# power_supply.net
KiCad netlist of a schematic drawn in Altium Designer
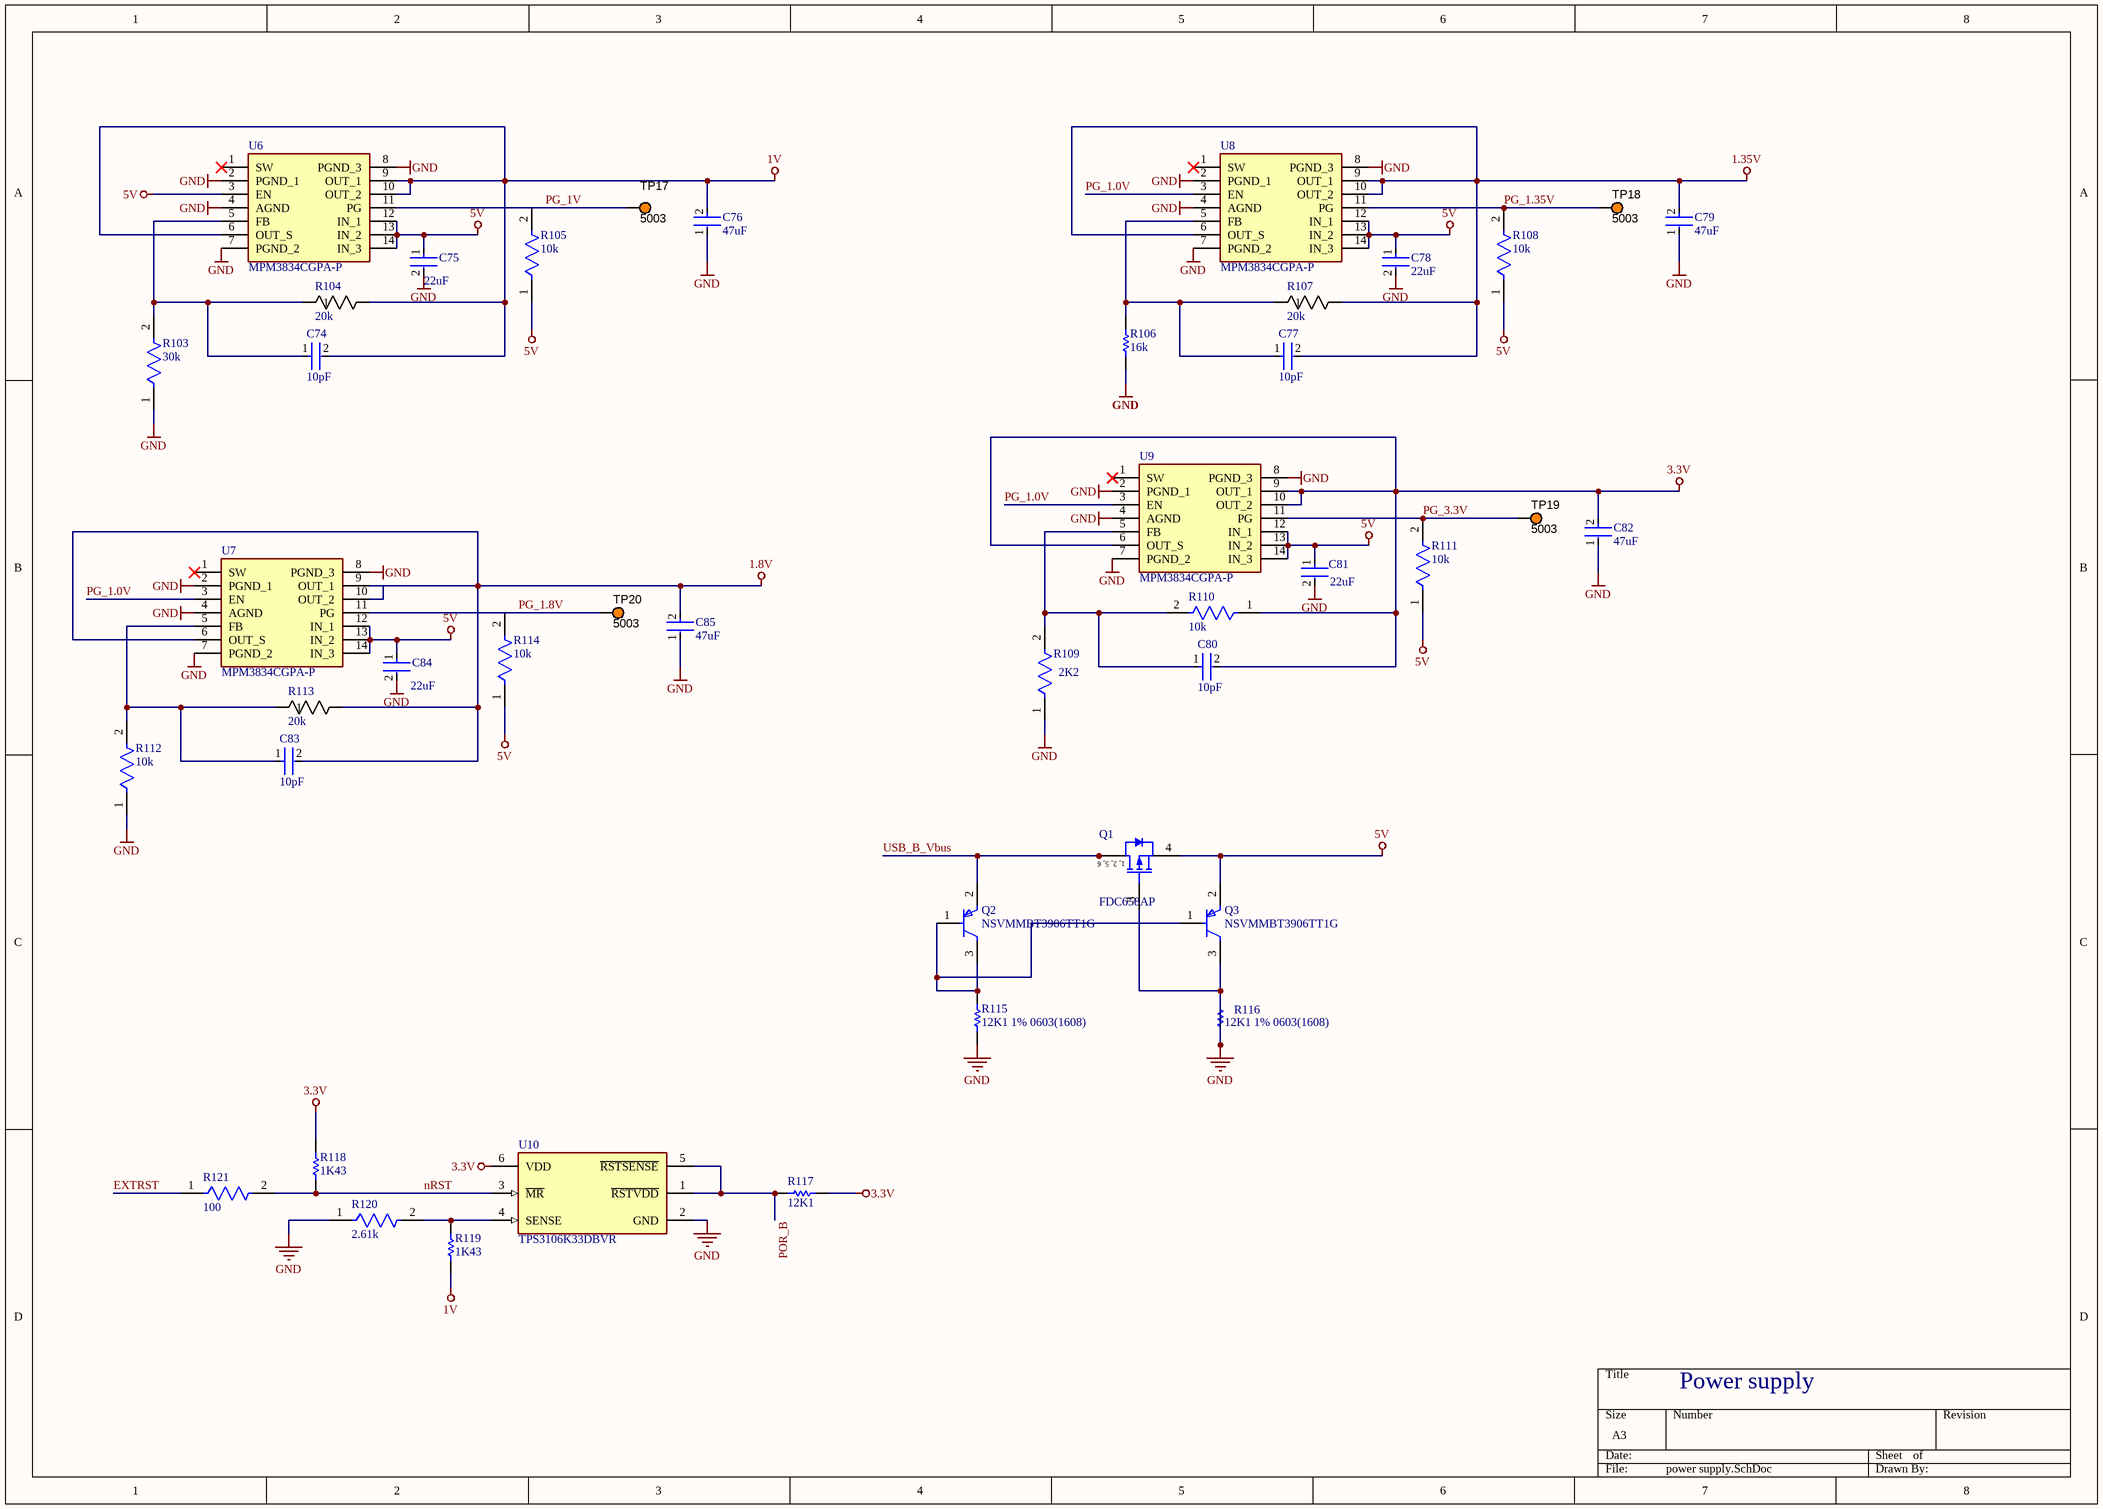
[diagram p0: power supply.SchDoc]

(export (version "E")
  (design (tool "Eeschema 10.0.6"))
  (components
    (comp (ref "C74")
      (value "10pF")
      (footprint "FP-0603-L_1_6_0_15-W_0_81-IPC_B")
      (description "General Purpose Ceramic Capacitor, 0603, 10pF, 2%, NP0, 30ppm/°C, 100V")
      (fields (field (name "TOLERANCE") "2%"))
      (libsource (lib "Altium Content Vault") (part "02cd4be3c70576c341d710602a673aa"))
    )
    (comp (ref "C75")
      (value "22uF")
      (footprint "FP-GRMJN7-0_1-IPC_C")
      (description "Chip Multilayer Ceramic Capacitors for General Purpose, 0704, 22uF, X5R, 15%, 20%, 16V")
      (libsource (lib "Altium Content Vault") (part "02cd4be3c70576c341d710602a673aa"))
    )
    (comp (ref "C76")
      (value "47uF")
      (footprint "FP-GRM31C-0_3-e0_3_0_8-IPC_C")
      (description "Chip Multilayer Ceramic Capacitors for General Purpose, 1206, 47uF, X5R, 15%, 20%, 16V")
      (fields (field (name "TOLERANCE") "20%"))
      (libsource (lib "Altium Content Vault") (part "f23184f103b6ebe33a8c269c53dcba6"))
    )
    (comp (ref "C77")
      (value "10pF")
      (footprint "FP-0603-L_1_6_0_15-W_0_81-IPC_B")
      (description "General Purpose Ceramic Capacitor, 0603, 10pF, 2%, NP0, 30ppm/°C, 100V")
      (fields (field (name "TOLERANCE") "2%"))
      (libsource (lib "Altium Content Vault") (part "02cd4be3c70576c341d710602a673aa"))
    )
    (comp (ref "C78")
      (value "22uF")
      (footprint "FP-GRMJN7-0_1-IPC_C")
      (description "Chip Multilayer Ceramic Capacitors for General Purpose, 0704, 22uF, X5R, 15%, 20%, 16V")
      (libsource (lib "Altium Content Vault") (part "02cd4be3c70576c341d710602a673aa"))
    )
    (comp (ref "C79")
      (value "47uF")
      (footprint "FP-GRM31C-0_3-e0_3_0_8-IPC_C")
      (description "Chip Multilayer Ceramic Capacitors for General Purpose, 1206, 47uF, X5R, 15%, 20%, 16V")
      (fields (field (name "TOLERANCE") "20%"))
      (libsource (lib "Altium Content Vault") (part "f23184f103b6ebe33a8c269c53dcba6"))
    )
    (comp (ref "C80")
      (value "10pF")
      (footprint "FP-0603-L_1_6_0_15-W_0_81-IPC_B")
      (description "General Purpose Ceramic Capacitor, 0603, 10pF, 2%, NP0, 30ppm/°C, 100V")
      (fields (field (name "TOLERANCE") "2%"))
      (libsource (lib "Altium Content Vault") (part "02cd4be3c70576c341d710602a673aa"))
    )
    (comp (ref "C81")
      (value "22uF")
      (footprint "FP-GRMJN7-0_1-IPC_C")
      (description "Chip Multilayer Ceramic Capacitors for General Purpose, 0704, 22uF, X5R, 15%, 20%, 16V")
      (libsource (lib "Altium Content Vault") (part "02cd4be3c70576c341d710602a673aa"))
    )
    (comp (ref "C82")
      (value "47uF")
      (footprint "FP-GRM31C-0_3-e0_3_0_8-IPC_C")
      (description "Chip Multilayer Ceramic Capacitors for General Purpose, 1206, 47uF, X5R, 15%, 20%, 16V")
      (fields (field (name "TOLERANCE") "20%"))
      (libsource (lib "Altium Content Vault") (part "f23184f103b6ebe33a8c269c53dcba6"))
    )
    (comp (ref "C83")
      (value "10pF")
      (footprint "FP-0603-L_1_6_0_15-W_0_81-IPC_B")
      (description "General Purpose Ceramic Capacitor, 0603, 10pF, 2%, NP0, 30ppm/°C, 100V")
      (fields (field (name "TOLERANCE") "2%"))
      (libsource (lib "Altium Content Vault") (part "02cd4be3c70576c341d710602a673aa"))
    )
    (comp (ref "C84")
      (value "22uF")
      (footprint "FP-GRMJN7-0_1-IPC_C")
      (description "Chip Multilayer Ceramic Capacitors for General Purpose, 0704, 22uF, X5R, 15%, 20%, 16V")
      (libsource (lib "Altium Content Vault") (part "02cd4be3c70576c341d710602a673aa"))
    )
    (comp (ref "C85")
      (value "47uF")
      (footprint "FP-GRM31C-0_3-e0_3_0_8-IPC_C")
      (description "Chip Multilayer Ceramic Capacitors for General Purpose, 1206, 47uF, X5R, 15%, 20%, 16V")
      (fields (field (name "TOLERANCE") "20%"))
      (libsource (lib "Altium Content Vault") (part "f23184f103b6ebe33a8c269c53dcba6"))
    )
    (comp (ref "Q1")
      (value "FDC658AP")
      (footprint "FAIR-SOT23-6_V")
      (fields (field (name "MANUFACTURER") "Fairchild Semiconductor"))
      (libsource (lib "Altium Content Vault") (part "PEMOS-DDGSDD-6"))
    )
    (comp (ref "Q2")
      (value "NSVMMBT3906TT1G")
      (footprint "FP-463-01-MFG")
      (description "NSVMMBT3906TT1G Small Signal Bipolar Transistor, 0.2A I(C), 40V V(BR)CEO, 1-Element, PNP, Silicon")
      (libsource (lib "Altium Content Vault") (part "ffd30bc5d0a750d7d7ef0ebafdf4ab0"))
    )
    (comp (ref "Q3")
      (value "NSVMMBT3906TT1G")
      (footprint "FP-463-01-MFG")
      (description "NSVMMBT3906TT1G Small Signal Bipolar Transistor, 0.2A I(C), 40V V(BR)CEO, 1-Element, PNP, Silicon")
      (libsource (lib "Altium Content Vault") (part "ffd30bc5d0a750d7d7ef0ebafdf4ab0"))
    )
    (comp (ref "R103")
      (value "30k")
      (footprint "FP-RMCF0603-IPC_A")
      (description "30kΩ ±5% 0.1W 0603 Thick Film Chip Resistor AEC-Q200 compliant")
      (fields (field (name "TOLERANCE") "5%"))
      (libsource (lib "Altium Content Vault") (part "1029c3af85768c4190bb7ad29bc67b5"))
    )
    (comp (ref "R104")
      (value "20k")
      (footprint "RES_RCC0402_VIS")
      (description "RCC040220K0FKED Res Thick Film 0402 20K Ohm 1% 0.125W(1/8W) ±100ppm/°C Pad SMD Automotive T/R")
      (libsource (lib "Altium Content Vault") (part "RCC040220K0FKED"))
    )
    (comp (ref "R105")
      (value "10k")
      (footprint "FP-RN73R2A-IPC_A")
      (description "RES 10K OHM 0.1% 1/8W 0805")
      (libsource (lib "Altium Content Vault") (part "1029c3af85768c4190bb7ad29bc67b5"))
    )
    (comp (ref "R106")
      (value "16k")
      (footprint "RESC0603X28X15LL05T05")
      (fields (field (name "PART NUMBER") "CRCW020116K0JNED") (field (name "MANUFACTURER") "Vishay Dale"))
      (libsource (lib "Altium Content Vault") (part "RES"))
    )
    (comp (ref "R107")
      (value "20k")
      (footprint "RES_RCC0402_VIS")
      (description "RCC040220K0FKED Res Thick Film 0402 20K Ohm 1% 0.125W(1/8W) ±100ppm/°C Pad SMD Automotive T/R")
      (libsource (lib "Altium Content Vault") (part "RCC040220K0FKED"))
    )
    (comp (ref "R108")
      (value "10k")
      (footprint "FP-RN73R2A-IPC_A")
      (description "RES 10K OHM 0.1% 1/8W 0805")
      (libsource (lib "Altium Content Vault") (part "1029c3af85768c4190bb7ad29bc67b5"))
    )
    (comp (ref "R109")
      (value "2K2")
      (footprint "FP-LTR10-IPC_B")
      (description "High power chip resistors wide terminal type 2.2kΩ 5% 0.25W 0508")
      (fields (field (name "TOLERANCE") "5%"))
      (libsource (lib "Altium Content Vault") (part "1029c3af85768c4190bb7ad29bc67b5"))
    )
    (comp (ref "R110")
      (value "10k")
      (footprint "FP-RN73R2A-IPC_A")
      (description "RES 10K OHM 0.1% 1/8W 0805")
      (libsource (lib "Altium Content Vault") (part "1029c3af85768c4190bb7ad29bc67b5"))
    )
    (comp (ref "R111")
      (value "10k")
      (footprint "FP-RN73R2A-IPC_A")
      (description "RES 10K OHM 0.1% 1/8W 0805")
      (libsource (lib "Altium Content Vault") (part "1029c3af85768c4190bb7ad29bc67b5"))
    )
    (comp (ref "R112")
      (value "10k")
      (footprint "FP-RN73R2A-IPC_A")
      (description "RES 10K OHM 0.1% 1/8W 0805")
      (libsource (lib "Altium Content Vault") (part "1029c3af85768c4190bb7ad29bc67b5"))
    )
    (comp (ref "R113")
      (value "20k")
      (footprint "RES_RCC0402_VIS")
      (description "RCC040220K0FKED Res Thick Film 0402 20K Ohm 1% 0.125W(1/8W) ±100ppm/°C Pad SMD Automotive T/R")
      (libsource (lib "Altium Content Vault") (part "RCC040220K0FKED"))
    )
    (comp (ref "R114")
      (value "10k")
      (footprint "FP-RN73R2A-IPC_A")
      (description "RES 10K OHM 0.1% 1/8W 0805")
      (libsource (lib "Altium Content Vault") (part "1029c3af85768c4190bb7ad29bc67b5"))
    )
    (comp (ref "R115")
      (value "12K1 1% 0603(1608)")
      (footprint "RESC0603(1608)_M")
      (description "12K1 0.1W 1% 0603 (1608 Metric)  SMD")
      (fields (field (name "POWER") "0.1 W") (field (name "TOLERANCE") "1 %"))
      (libsource (lib "Altium Content Vault") (part "RES"))
    )
    (comp (ref "R116")
      (value "12K1 1% 0603(1608)")
      (footprint "RESC0603(1608)_M")
      (description "12K1 0.1W 1% 0603 (1608 Metric)  SMD")
      (fields (field (name "POWER") "0.1 W") (field (name "TOLERANCE") "1 %"))
      (libsource (lib "Altium Content Vault") (part "RES"))
    )
    (comp (ref "R117")
      (value "12K1")
      (footprint "RESC0603(1608)_M")
      (description "12K1 0.1W 1% 0603 (1608 Metric)  SMD")
      (fields (field (name "POWER") "0.1 W") (field (name "TOLERANCE") "1 %"))
      (libsource (lib "Altium Content Vault") (part "RES"))
    )
    (comp (ref "R118")
      (value "1K43")
      (footprint "RESC1206(3216)_M")
      (description "1K43 0.25W 1% 1206 (3216 Metric)  SMD")
      (fields (field (name "POWER") "0.25 W") (field (name "TOLERANCE") "1 %"))
      (libsource (lib "Altium Content Vault") (part "RES"))
    )
    (comp (ref "R119")
      (value "1K43")
      (footprint "RESC1206(3216)_M")
      (description "1K43 0.25W 1% 1206 (3216 Metric)  SMD")
      (fields (field (name "POWER") "0.25 W") (field (name "TOLERANCE") "1 %"))
      (libsource (lib "Altium Content Vault") (part "RES"))
    )
    (comp (ref "R120")
      (value "2.61k")
      (footprint "FP-RK73H1J-IPC_B")
      (description "2.61kΩ ±0.5% 0.1W Chip Resistor 0603 Thick Film AEC-Q200 Qualified")
      (libsource (lib "Altium Content Vault") (part "1029c3af85768c4190bb7ad29bc67b5"))
    )
    (comp (ref "R121")
      (value "100")
      (footprint "FP-RMCF0805-IPC_A")
      (description "100Ω ±1% 0.125W 0805 Thick Film Chip Resistor AEC-Q200 compliant")
      (fields (field (name "TOLERANCE") "1%"))
      (libsource (lib "Altium Content Vault") (part "1029c3af85768c4190bb7ad29bc67b5"))
    )
    (comp (ref "TP17")
      (value "5003")
      (footprint "KSTN-5003")
      (description "Test Point, Orange, 1-Pin THD, RoHS")
      (libsource (lib "Altium Content Vault") (part "TESTPOINT_ORANGE"))
    )
    (comp (ref "TP18")
      (value "5003")
      (footprint "KSTN-5003")
      (description "Test Point, Orange, 1-Pin THD, RoHS")
      (libsource (lib "Altium Content Vault") (part "TESTPOINT_ORANGE"))
    )
    (comp (ref "TP19")
      (value "5003")
      (footprint "KSTN-5003")
      (description "Test Point, Orange, 1-Pin THD, RoHS")
      (libsource (lib "Altium Content Vault") (part "TESTPOINT_ORANGE"))
    )
    (comp (ref "TP20")
      (value "5003")
      (footprint "KSTN-5003")
      (description "Test Point, Orange, 1-Pin THD, RoHS")
      (libsource (lib "Altium Content Vault") (part "TESTPOINT_ORANGE"))
    )
    (comp (ref "U6")
      (value "MPM3834CGPA-P")
      (footprint "SamacSys:MPM3834CGPAP")
      (description "Integrated Circuit")
      (fields (field (name "MOUSER PART NUMBER") "946-MPM3834CGPA-P"))
      (libsource (lib "*") (part "MPM3834CGPA-P"))
    )
    (comp (ref "U7")
      (value "MPM3834CGPA-P")
      (footprint "SamacSys:MPM3834CGPAP")
      (description "Integrated Circuit")
      (fields (field (name "MOUSER PART NUMBER") "946-MPM3834CGPA-P"))
      (libsource (lib "*") (part "MPM3834CGPA-P"))
    )
    (comp (ref "U8")
      (value "MPM3834CGPA-P")
      (footprint "SamacSys:MPM3834CGPAP")
      (description "Integrated Circuit")
      (fields (field (name "MOUSER PART NUMBER") "946-MPM3834CGPA-P"))
      (libsource (lib "*") (part "MPM3834CGPA-P"))
    )
    (comp (ref "U9")
      (value "MPM3834CGPA-P")
      (footprint "SamacSys:MPM3834CGPAP")
      (description "Integrated Circuit")
      (fields (field (name "MOUSER PART NUMBER") "946-MPM3834CGPA-P"))
      (libsource (lib "*") (part "MPM3834CGPA-P"))
    )
    (comp (ref "U10")
      (value "TPS3106K33DBVR")
      (footprint "FP-DBV0006A-MFG")
      (description "IC SUPERVISORY CIRCUIT SOT-23-6")
      (fields
        (field (name "OCTOPART") "https://octopart.com/tps3106k33dbvr-texas+instruments-505820")
        (field (name "MANUFACTURER") "Texas Instruments")
      )
      (libsource (lib "Altium Content Vault") (part "1e400620819f6d8b17379bded79418f"))
    )
  )
  (nets
    (net (code "1") (name "/EXTRST") (class "Default")
      (node (ref "R121") (pin "1") (pinfunction "1_1") (pintype "passive"))
    )
    (net (code "2") (name "/PG_1.0V") (class "Default")
      (node (ref "U7") (pin "3") (pinfunction "EN_3") (pintype "passive"))
      (node (ref "U8") (pin "3") (pinfunction "EN_3") (pintype "passive"))
      (node (ref "U9") (pin "3") (pinfunction "EN_3") (pintype "passive"))
    )
    (net (code "3") (name "/PG_1.8V") (class "Default")
      (node (ref "R114") (pin "2") (pinfunction "2_2") (pintype "passive"))
      (node (ref "TP20") (pin "1") (pinfunction "1_1") (pintype "passive"))
      (node (ref "U7") (pin "11") (pinfunction "PG_11") (pintype "passive"))
    )
    (net (code "4") (name "/PG_1.35V") (class "Default")
      (node (ref "R108") (pin "2") (pinfunction "2_2") (pintype "passive"))
      (node (ref "TP18") (pin "1") (pinfunction "1_1") (pintype "passive"))
      (node (ref "U8") (pin "11") (pinfunction "PG_11") (pintype "passive"))
    )
    (net (code "5") (name "/PG_1V") (class "Default")
      (node (ref "R105") (pin "2") (pinfunction "2_2") (pintype "passive"))
      (node (ref "TP17") (pin "1") (pinfunction "1_1") (pintype "passive"))
      (node (ref "U6") (pin "11") (pinfunction "PG_11") (pintype "passive"))
    )
    (net (code "6") (name "/PG_3.3V") (class "Default")
      (node (ref "R111") (pin "2") (pinfunction "2_2") (pintype "passive"))
      (node (ref "TP19") (pin "1") (pinfunction "1_1") (pintype "passive"))
      (node (ref "U9") (pin "11") (pinfunction "PG_11") (pintype "passive"))
    )
    (net (code "7") (name "/POR_B") (class "Default")
      (node (ref "R117") (pin "2") (pinfunction "2_2") (pintype "passive"))
      (node (ref "U10") (pin "1") (pinfunction "~{RSTVDD}_1") (pintype "open_collector"))
      (node (ref "U10") (pin "5") (pinfunction "~{RSTSENSE}_5") (pintype "open_collector"))
    )
    (net (code "8") (name "/USB_B_Vbus") (class "Default")
      (node (ref "Q1") (pin "1") (pinfunction "DRAIN_1") (pintype "passive"))
      (node (ref "Q1") (pin "2") (pinfunction "DRAIN_2") (pintype "passive"))
      (node (ref "Q1") (pin "5") (pinfunction "DRAIN_5") (pintype "passive"))
      (node (ref "Q1") (pin "6") (pinfunction "DRAIN_6") (pintype "passive"))
      (node (ref "Q2") (pin "2") (pinfunction "E_2") (pintype "passive"))
    )
    (net (code "9") (name "/nRST") (class "Default")
      (node (ref "R118") (pin "1") (pinfunction "1_1") (pintype "passive"))
      (node (ref "R121") (pin "2") (pinfunction "2_2") (pintype "passive"))
      (node (ref "U10") (pin "3") (pinfunction "~{MR}_3") (pintype "input"))
    )
    (net (code "10") (name "1.8V") (class "Default")
      (node (ref "C83") (pin "2") (pinfunction "2_2") (pintype "passive"))
      (node (ref "C85") (pin "2") (pinfunction "2_2") (pintype "passive"))
      (node (ref "R113") (pin "2") (pinfunction "2_2") (pintype "passive"))
      (node (ref "U7") (pin "10") (pinfunction "OUT_2_10") (pintype "passive"))
      (node (ref "U7") (pin "6") (pinfunction "OUT_S_6") (pintype "passive"))
      (node (ref "U7") (pin "9") (pinfunction "OUT_1_9") (pintype "passive"))
    )
    (net (code "11") (name "1.35V") (class "Default")
      (node (ref "C77") (pin "2") (pinfunction "2_2") (pintype "passive"))
      (node (ref "C79") (pin "2") (pinfunction "2_2") (pintype "passive"))
      (node (ref "R107") (pin "2") (pinfunction "2_2") (pintype "passive"))
      (node (ref "U8") (pin "10") (pinfunction "OUT_2_10") (pintype "passive"))
      (node (ref "U8") (pin "6") (pinfunction "OUT_S_6") (pintype "passive"))
      (node (ref "U8") (pin "9") (pinfunction "OUT_1_9") (pintype "passive"))
    )
    (net (code "12") (name "1V") (class "Default")
      (node (ref "C74") (pin "2") (pinfunction "2_2") (pintype "passive"))
      (node (ref "C76") (pin "2") (pinfunction "2_2") (pintype "passive"))
      (node (ref "R104") (pin "2") (pinfunction "2_2") (pintype "passive"))
      (node (ref "R119") (pin "1") (pinfunction "1_1") (pintype "passive"))
      (node (ref "U6") (pin "10") (pinfunction "OUT_2_10") (pintype "passive"))
      (node (ref "U6") (pin "6") (pinfunction "OUT_S_6") (pintype "passive"))
      (node (ref "U6") (pin "9") (pinfunction "OUT_1_9") (pintype "passive"))
    )
    (net (code "13") (name "3.3V") (class "Default")
      (node (ref "C80") (pin "2") (pinfunction "2_2") (pintype "passive"))
      (node (ref "C82") (pin "2") (pinfunction "2_2") (pintype "passive"))
      (node (ref "R110") (pin "1") (pinfunction "1_1") (pintype "passive"))
      (node (ref "R117") (pin "1") (pinfunction "1_1") (pintype "passive"))
      (node (ref "R118") (pin "2") (pinfunction "2_2") (pintype "passive"))
      (node (ref "U10") (pin "6") (pinfunction "VDD_6") (pintype "power_in"))
      (node (ref "U9") (pin "10") (pinfunction "OUT_2_10") (pintype "passive"))
      (node (ref "U9") (pin "6") (pinfunction "OUT_S_6") (pintype "passive"))
      (node (ref "U9") (pin "9") (pinfunction "OUT_1_9") (pintype "passive"))
    )
    (net (code "14") (name "5V") (class "Default")
      (node (ref "C75") (pin "1") (pinfunction "1_1") (pintype "passive"))
      (node (ref "C78") (pin "1") (pinfunction "1_1") (pintype "passive"))
      (node (ref "C81") (pin "1") (pinfunction "1_1") (pintype "passive"))
      (node (ref "C84") (pin "1") (pinfunction "1_1") (pintype "passive"))
      (node (ref "Q1") (pin "4") (pinfunction "SOURCE_4") (pintype "passive"))
      (node (ref "Q3") (pin "2") (pinfunction "E_2") (pintype "passive"))
      (node (ref "R105") (pin "1") (pinfunction "1_1") (pintype "passive"))
      (node (ref "R108") (pin "1") (pinfunction "1_1") (pintype "passive"))
      (node (ref "R111") (pin "1") (pinfunction "1_1") (pintype "passive"))
      (node (ref "R114") (pin "1") (pinfunction "1_1") (pintype "passive"))
      (node (ref "U6") (pin "12") (pinfunction "IN_1_12") (pintype "passive"))
      (node (ref "U6") (pin "13") (pinfunction "IN_2_13") (pintype "passive"))
      (node (ref "U6") (pin "14") (pinfunction "IN_3_14") (pintype "passive"))
      (node (ref "U6") (pin "3") (pinfunction "EN_3") (pintype "passive"))
      (node (ref "U7") (pin "12") (pinfunction "IN_1_12") (pintype "passive"))
      (node (ref "U7") (pin "13") (pinfunction "IN_2_13") (pintype "passive"))
      (node (ref "U7") (pin "14") (pinfunction "IN_3_14") (pintype "passive"))
      (node (ref "U8") (pin "12") (pinfunction "IN_1_12") (pintype "passive"))
      (node (ref "U8") (pin "13") (pinfunction "IN_2_13") (pintype "passive"))
      (node (ref "U8") (pin "14") (pinfunction "IN_3_14") (pintype "passive"))
      (node (ref "U9") (pin "12") (pinfunction "IN_1_12") (pintype "passive"))
      (node (ref "U9") (pin "13") (pinfunction "IN_2_13") (pintype "passive"))
      (node (ref "U9") (pin "14") (pinfunction "IN_3_14") (pintype "passive"))
    )
    (net (code "15") (name "GND") (class "Default")
      (node (ref "C75") (pin "2") (pinfunction "2_2") (pintype "passive"))
      (node (ref "C76") (pin "1") (pinfunction "1_1") (pintype "passive"))
      (node (ref "C78") (pin "2") (pinfunction "2_2") (pintype "passive"))
      (node (ref "C79") (pin "1") (pinfunction "1_1") (pintype "passive"))
      (node (ref "C81") (pin "2") (pinfunction "2_2") (pintype "passive"))
      (node (ref "C82") (pin "1") (pinfunction "1_1") (pintype "passive"))
      (node (ref "C84") (pin "2") (pinfunction "2_2") (pintype "passive"))
      (node (ref "C85") (pin "1") (pinfunction "1_1") (pintype "passive"))
      (node (ref "Q1") (pin "3") (pinfunction "GATE_3") (pintype "passive"))
      (node (ref "Q3") (pin "3") (pinfunction "C_3") (pintype "passive"))
      (node (ref "R103") (pin "1") (pinfunction "1_1") (pintype "passive"))
      (node (ref "R106") (pin "1") (pinfunction "1_1") (pintype "passive"))
      (node (ref "R109") (pin "1") (pinfunction "1_1") (pintype "passive"))
      (node (ref "R112") (pin "1") (pinfunction "1_1") (pintype "passive"))
      (node (ref "R115") (pin "1") (pinfunction "1_1") (pintype "passive"))
      (node (ref "R116") (pin "1") (pinfunction "1_1") (pintype "passive"))
      (node (ref "R116") (pin "2") (pinfunction "2_2") (pintype "passive"))
      (node (ref "R120") (pin "1") (pinfunction "1_1") (pintype "passive"))
      (node (ref "U10") (pin "2") (pinfunction "GND_2") (pintype "power_in"))
      (node (ref "U6") (pin "2") (pinfunction "PGND_1_2") (pintype "passive"))
      (node (ref "U6") (pin "4") (pinfunction "AGND_4") (pintype "passive"))
      (node (ref "U6") (pin "7") (pinfunction "PGND_2_7") (pintype "passive"))
      (node (ref "U6") (pin "8") (pinfunction "PGND_3_8") (pintype "passive"))
      (node (ref "U7") (pin "2") (pinfunction "PGND_1_2") (pintype "passive"))
      (node (ref "U7") (pin "4") (pinfunction "AGND_4") (pintype "passive"))
      (node (ref "U7") (pin "7") (pinfunction "PGND_2_7") (pintype "passive"))
      (node (ref "U7") (pin "8") (pinfunction "PGND_3_8") (pintype "passive"))
      (node (ref "U8") (pin "2") (pinfunction "PGND_1_2") (pintype "passive"))
      (node (ref "U8") (pin "4") (pinfunction "AGND_4") (pintype "passive"))
      (node (ref "U8") (pin "7") (pinfunction "PGND_2_7") (pintype "passive"))
      (node (ref "U8") (pin "8") (pinfunction "PGND_3_8") (pintype "passive"))
      (node (ref "U9") (pin "2") (pinfunction "PGND_1_2") (pintype "passive"))
      (node (ref "U9") (pin "4") (pinfunction "AGND_4") (pintype "passive"))
      (node (ref "U9") (pin "7") (pinfunction "PGND_2_7") (pintype "passive"))
      (node (ref "U9") (pin "8") (pinfunction "PGND_3_8") (pintype "passive"))
    )
    (net (code "16") (name "Net-(Q2-B)") (class "Default")
      (node (ref "Q2") (pin "1") (pinfunction "B_1") (pintype "passive"))
      (node (ref "Q2") (pin "3") (pinfunction "C_3") (pintype "passive"))
      (node (ref "Q3") (pin "1") (pinfunction "B_1") (pintype "passive"))
      (node (ref "R115") (pin "2") (pinfunction "2_2") (pintype "passive"))
    )
    (net (code "17") (name "Net-(U6-FB)") (class "Default")
      (node (ref "C74") (pin "1") (pinfunction "1_1") (pintype "passive"))
      (node (ref "R103") (pin "2") (pinfunction "2_2") (pintype "passive"))
      (node (ref "R104") (pin "1") (pinfunction "1_1") (pintype "passive"))
      (node (ref "U6") (pin "5") (pinfunction "FB_5") (pintype "passive"))
    )
    (net (code "18") (name "Net-(U7-FB)") (class "Default")
      (node (ref "C83") (pin "1") (pinfunction "1_1") (pintype "passive"))
      (node (ref "R112") (pin "2") (pinfunction "2_2") (pintype "passive"))
      (node (ref "R113") (pin "1") (pinfunction "1_1") (pintype "passive"))
      (node (ref "U7") (pin "5") (pinfunction "FB_5") (pintype "passive"))
    )
    (net (code "19") (name "Net-(U8-FB)") (class "Default")
      (node (ref "C77") (pin "1") (pinfunction "1_1") (pintype "passive"))
      (node (ref "R106") (pin "2") (pinfunction "2_2") (pintype "passive"))
      (node (ref "R107") (pin "1") (pinfunction "1_1") (pintype "passive"))
      (node (ref "U8") (pin "5") (pinfunction "FB_5") (pintype "passive"))
    )
    (net (code "20") (name "Net-(U9-FB)") (class "Default")
      (node (ref "C80") (pin "1") (pinfunction "1_1") (pintype "passive"))
      (node (ref "R109") (pin "2") (pinfunction "2_2") (pintype "passive"))
      (node (ref "R110") (pin "2") (pinfunction "2_2") (pintype "passive"))
      (node (ref "U9") (pin "5") (pinfunction "FB_5") (pintype "passive"))
    )
    (net (code "21") (name "Net-(U10-SENSE)") (class "Default")
      (node (ref "R119") (pin "2") (pinfunction "2_2") (pintype "passive"))
      (node (ref "R120") (pin "2") (pinfunction "2_2") (pintype "passive"))
      (node (ref "U10") (pin "4") (pinfunction "SENSE_4") (pintype "input"))
    )
    (net (code "22") (name "unconnected-(U6-SW-Pad1)") (class "Default")
      (node (ref "U6") (pin "1") (pinfunction "SW_1") (pintype "passive+no_connect"))
    )
    (net (code "23") (name "unconnected-(U7-SW-Pad1)") (class "Default")
      (node (ref "U7") (pin "1") (pinfunction "SW_1") (pintype "passive+no_connect"))
    )
    (net (code "24") (name "unconnected-(U8-SW-Pad1)") (class "Default")
      (node (ref "U8") (pin "1") (pinfunction "SW_1") (pintype "passive+no_connect"))
    )
    (net (code "25") (name "unconnected-(U9-SW-Pad1)") (class "Default")
      (node (ref "U9") (pin "1") (pinfunction "SW_1") (pintype "passive+no_connect"))
    )
  )
)
